# 12_-_RELAYS.net
KiCad netlist of a schematic drawn in Altium Designer
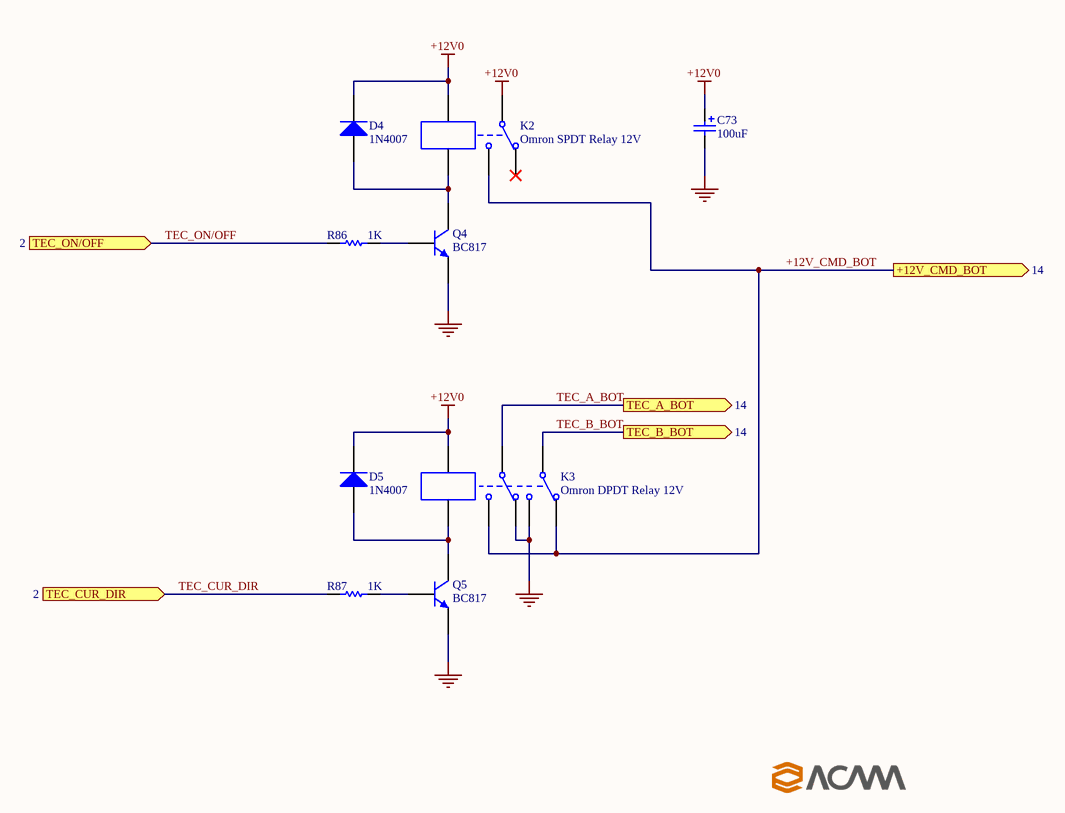
[diagram p0: [12] - RELAYS.SchDoc]

(export (version "E")
  (design (tool "Eeschema 10.0.6"))
  (components
    (comp (ref "C73")
      (value "100uF")
      (footprint "WCAP-ASLI_6.3x5.5")
      (description "Aluminium Electrolytic Capacitor")
      (libsource (lib "Farzan Custom Library") (part "Cap Aluminium Electrolytic"))
    )
    (comp (ref "D4")
      (value "1N4007")
      (footprint "SMA")
      (description "Diode")
      (libsource (lib "Farzan Custom Library") (part "Diode"))
    )
    (comp (ref "D5")
      (value "1N4007")
      (footprint "SMA")
      (description "Diode")
      (libsource (lib "Farzan Custom Library") (part "Diode"))
    )
    (comp (ref "K2")
      (value "Omron SPDT Relay 12V")
      (footprint "RELAY_SPDT")
      (description "Omron Single-Pole Dual-Throw Relay")
      (fields (field (name "MANUFACTURER PART NUM") "G2R-1-DC12"))
      (libsource (lib "Farzan Custom Library") (part "Relay-SPDT"))
    )
    (comp (ref "K3")
      (value "Omron DPDT Relay 12V")
      (footprint "RELAY_DPDT")
      (description "Omron Dual-Pole Dual-Throw Relay")
      (fields (field (name "MANUFACTURER PART NUM") "G2R-2-DC12"))
      (libsource (lib "Farzan Custom Library") (part "Relay-DPDT"))
    )
    (comp (ref "Q4")
      (value "BC817")
      (footprint "SOT23")
      (description "NPN General Purpose Transistor")
      (libsource (lib "Farzan Custom Library") (part "Transistor NPN"))
    )
    (comp (ref "Q5")
      (value "BC817")
      (footprint "SOT23")
      (description "NPN General Purpose Transistor")
      (libsource (lib "Farzan Custom Library") (part "Transistor NPN"))
    )
    (comp (ref "R86")
      (value "1K")
      (footprint "0402_R")
      (description "SMD Resistor")
      (fields (field (name "TOLERANCE") "5%"))
      (libsource (lib "Farzan Custom Library") (part "Res SMD"))
    )
    (comp (ref "R87")
      (value "1K")
      (footprint "0402_R")
      (description "SMD Resistor")
      (fields (field (name "TOLERANCE") "5%"))
      (libsource (lib "Farzan Custom Library") (part "Res SMD"))
    )
  )
  (nets
    (net (code "1") (name "+12V0") (class "Default")
      (node (ref "C73") (pin "1") (pinfunction "1_1") (pintype "passive"))
      (node (ref "D4") (pin "2") (pinfunction "K_2") (pintype "passive"))
      (node (ref "D5") (pin "2") (pinfunction "K_2") (pintype "passive"))
      (node (ref "K2") (pin "1") (pinfunction "Coil-A_1") (pintype "passive"))
      (node (ref "K2") (pin "4") (pinfunction "COM_4") (pintype "passive"))
      (node (ref "K3") (pin "1") (pinfunction "Coil-A_1") (pintype "passive"))
    )
    (net (code "2") (name "/+12V_CMD_BOT") (class "Default")
      (node (ref "K2") (pin "3") (pinfunction "NO_3") (pintype "passive"))
      (node (ref "K3") (pin "4") (pinfunction "Pole_1_NO_4") (pintype "passive"))
      (node (ref "K3") (pin "7") (pinfunction "Pole_2_NC_7") (pintype "passive"))
    )
    (net (code "3") (name "/TEC_A_BOT") (class "Default")
      (node (ref "K3") (pin "3") (pinfunction "Pole_1_COM_3") (pintype "passive"))
    )
    (net (code "4") (name "/TEC_B_BOT") (class "Default")
      (node (ref "K3") (pin "6") (pinfunction "Pole_2_COM_6") (pintype "passive"))
    )
    (net (code "5") (name "/TEC_CUR_DIR") (class "Default")
      (node (ref "R87") (pin "1") (pinfunction "1_1") (pintype "passive"))
    )
    (net (code "6") (name "/TEC_ON{slash}OFF") (class "Default")
      (node (ref "R86") (pin "1") (pinfunction "1_1") (pintype "passive"))
    )
    (net (code "7") (name "GND") (class "Default")
      (node (ref "C73") (pin "2") (pinfunction "2_2") (pintype "passive"))
      (node (ref "K3") (pin "2") (pinfunction "Pole_1_NC_2") (pintype "passive"))
      (node (ref "K3") (pin "5") (pinfunction "Pole_2_NO_5") (pintype "passive"))
      (node (ref "Q4") (pin "2") (pinfunction "E_2") (pintype "passive"))
      (node (ref "Q5") (pin "2") (pinfunction "E_2") (pintype "passive"))
    )
    (net (code "8") (name "Net-(D4-A)") (class "Default")
      (node (ref "D4") (pin "1") (pinfunction "A_1") (pintype "passive"))
      (node (ref "K2") (pin "5") (pinfunction "Coil-B_5") (pintype "passive"))
      (node (ref "Q4") (pin "3") (pinfunction "C_3") (pintype "passive"))
    )
    (net (code "9") (name "Net-(D5-A)") (class "Default")
      (node (ref "D5") (pin "1") (pinfunction "A_1") (pintype "passive"))
      (node (ref "K3") (pin "8") (pinfunction "Coil-B_8") (pintype "passive"))
      (node (ref "Q5") (pin "3") (pinfunction "C_3") (pintype "passive"))
    )
    (net (code "10") (name "Net-(Q4-B)") (class "Default")
      (node (ref "Q4") (pin "1") (pinfunction "B_1") (pintype "passive"))
      (node (ref "R86") (pin "2") (pinfunction "2_2") (pintype "passive"))
    )
    (net (code "11") (name "Net-(Q5-B)") (class "Default")
      (node (ref "Q5") (pin "1") (pinfunction "B_1") (pintype "passive"))
      (node (ref "R87") (pin "2") (pinfunction "2_2") (pintype "passive"))
    )
    (net (code "12") (name "unconnected-(K2-NC-Pad2)") (class "Default")
      (node (ref "K2") (pin "2") (pinfunction "NC_2") (pintype "passive+no_connect"))
    )
  )
)
